# Inertial_systems.net
KiCad netlist of a schematic drawn in Altium Designer
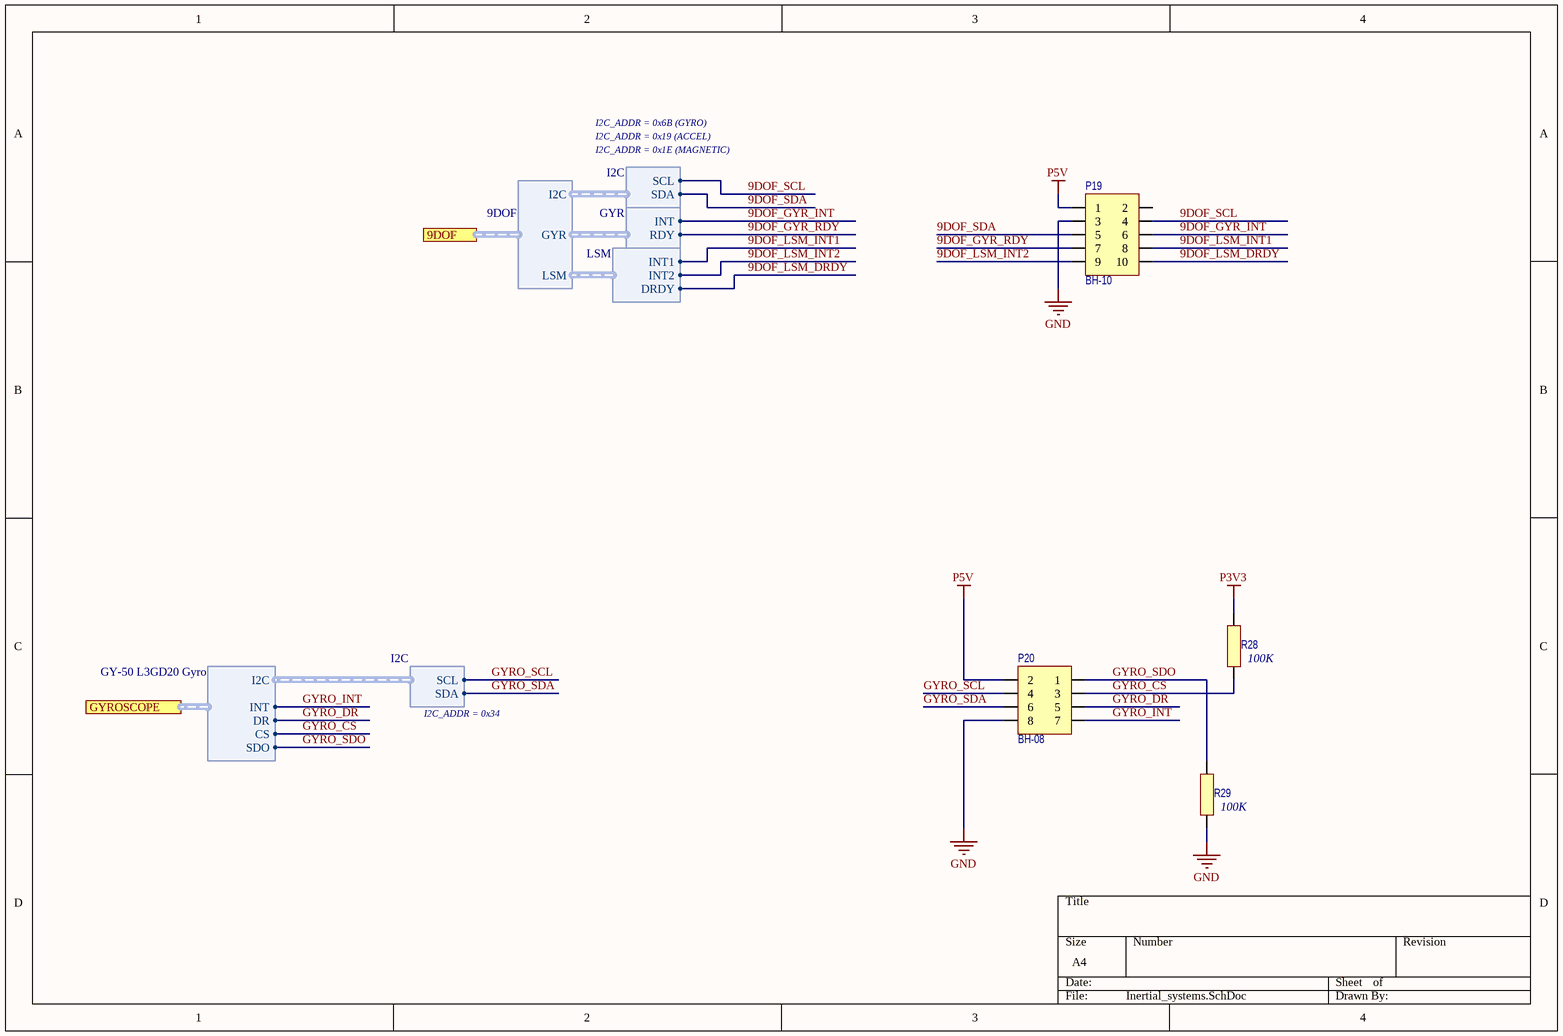
[diagram p0: Inertial_systems.SchDoc]

(export (version "E")
  (design (tool "Eeschema 10.0.6"))
  (components
    (comp (ref "P19") (value "BH-10") (footprint "BH-10") (libsource (lib "my_AP_lib_sch") (part "BH-10")))
    (comp (ref "P20") (value "BH-08") (footprint "BH-08") (libsource (lib "my_AP_lib_sch") (part "BH-08")))
    (comp (ref "R28")
      (value "100K")
      (footprint "R0805")
      (fields (field (name "Comment") "R0805"))
      (libsource (lib "my_AP_lib_sch") (part "R0805"))
    )
    (comp (ref "R29")
      (value "100K")
      (footprint "R0805")
      (fields (field (name "Comment") "R0805"))
      (libsource (lib "my_AP_lib_sch") (part "R0805"))
    )
  )
  (nets
    (net (code "8") (name "/9DOF_GYR_INT") (class "Default")
      (node (ref "P19") (pin "6") (pinfunction "6_6") (pintype "passive"))
    )
    (net (code "9") (name "/9DOF_GYR_RDY") (class "Default")
      (node (ref "P19") (pin "7") (pinfunction "7_7") (pintype "passive"))
    )
    (net (code "10") (name "/9DOF_LSM_DRDY") (class "Default")
      (node (ref "P19") (pin "10") (pinfunction "10_10") (pintype "passive"))
    )
    (net (code "11") (name "/9DOF_LSM_INT1") (class "Default")
      (node (ref "P19") (pin "8") (pinfunction "8_8") (pintype "passive"))
    )
    (net (code "12") (name "/9DOF_LSM_INT2") (class "Default")
      (node (ref "P19") (pin "9") (pinfunction "9_9") (pintype "passive"))
    )
    (net (code "13") (name "/9DOF_SCL") (class "Default")
      (node (ref "P19") (pin "4") (pinfunction "4_4") (pintype "passive"))
    )
    (net (code "14") (name "/9DOF_SDA") (class "Default")
      (node (ref "P19") (pin "5") (pinfunction "5_5") (pintype "passive"))
    )
    (net (code "17") (name "/GYRO_CS") (class "Default")
      (node (ref "P20") (pin "3") (pinfunction "3_3") (pintype "passive"))
      (node (ref "R28") (pin "1") (pinfunction "1_1") (pintype "passive"))
    )
    (net (code "18") (name "/GYRO_DR") (class "Default")
      (node (ref "P20") (pin "5") (pinfunction "5_5") (pintype "passive"))
    )
    (net (code "19") (name "/GYRO_INT") (class "Default")
      (node (ref "P20") (pin "7") (pinfunction "7_7") (pintype "passive"))
    )
    (net (code "20") (name "/GYRO_SCL") (class "Default")
      (node (ref "P20") (pin "4") (pinfunction "4_4") (pintype "passive"))
    )
    (net (code "21") (name "/GYRO_SDA") (class "Default")
      (node (ref "P20") (pin "6") (pinfunction "6_6") (pintype "passive"))
    )
    (net (code "22") (name "/GYRO_SDO") (class "Default")
      (node (ref "P20") (pin "1") (pinfunction "1_1") (pintype "passive"))
      (node (ref "R29") (pin "2") (pinfunction "2_2") (pintype "passive"))
    )
    (net (code "26") (name "GND") (class "Default")
      (node (ref "P19") (pin "3") (pinfunction "3_3") (pintype "passive"))
      (node (ref "P20") (pin "8") (pinfunction "8_8") (pintype "passive"))
      (node (ref "R29") (pin "1") (pinfunction "1_1") (pintype "passive"))
    )
    (net (code "27") (name "P3V3") (class "Default")
      (node (ref "R28") (pin "2") (pinfunction "2_2") (pintype "passive"))
    )
    (net (code "28") (name "P5V") (class "Default")
      (node (ref "P19") (pin "1") (pinfunction "1_1") (pintype "passive"))
      (node (ref "P20") (pin "2") (pinfunction "2_2") (pintype "passive"))
    )
    (net (code "29") (name "unconnected-(P19-Pad2)") (class "Default")
      (node (ref "P19") (pin "2") (pinfunction "2_2") (pintype "passive"))
    )
  )
)
